# Adafruit_Cobbler_Plus.net
KiCad netlist of a schematic drawn in EAGLE
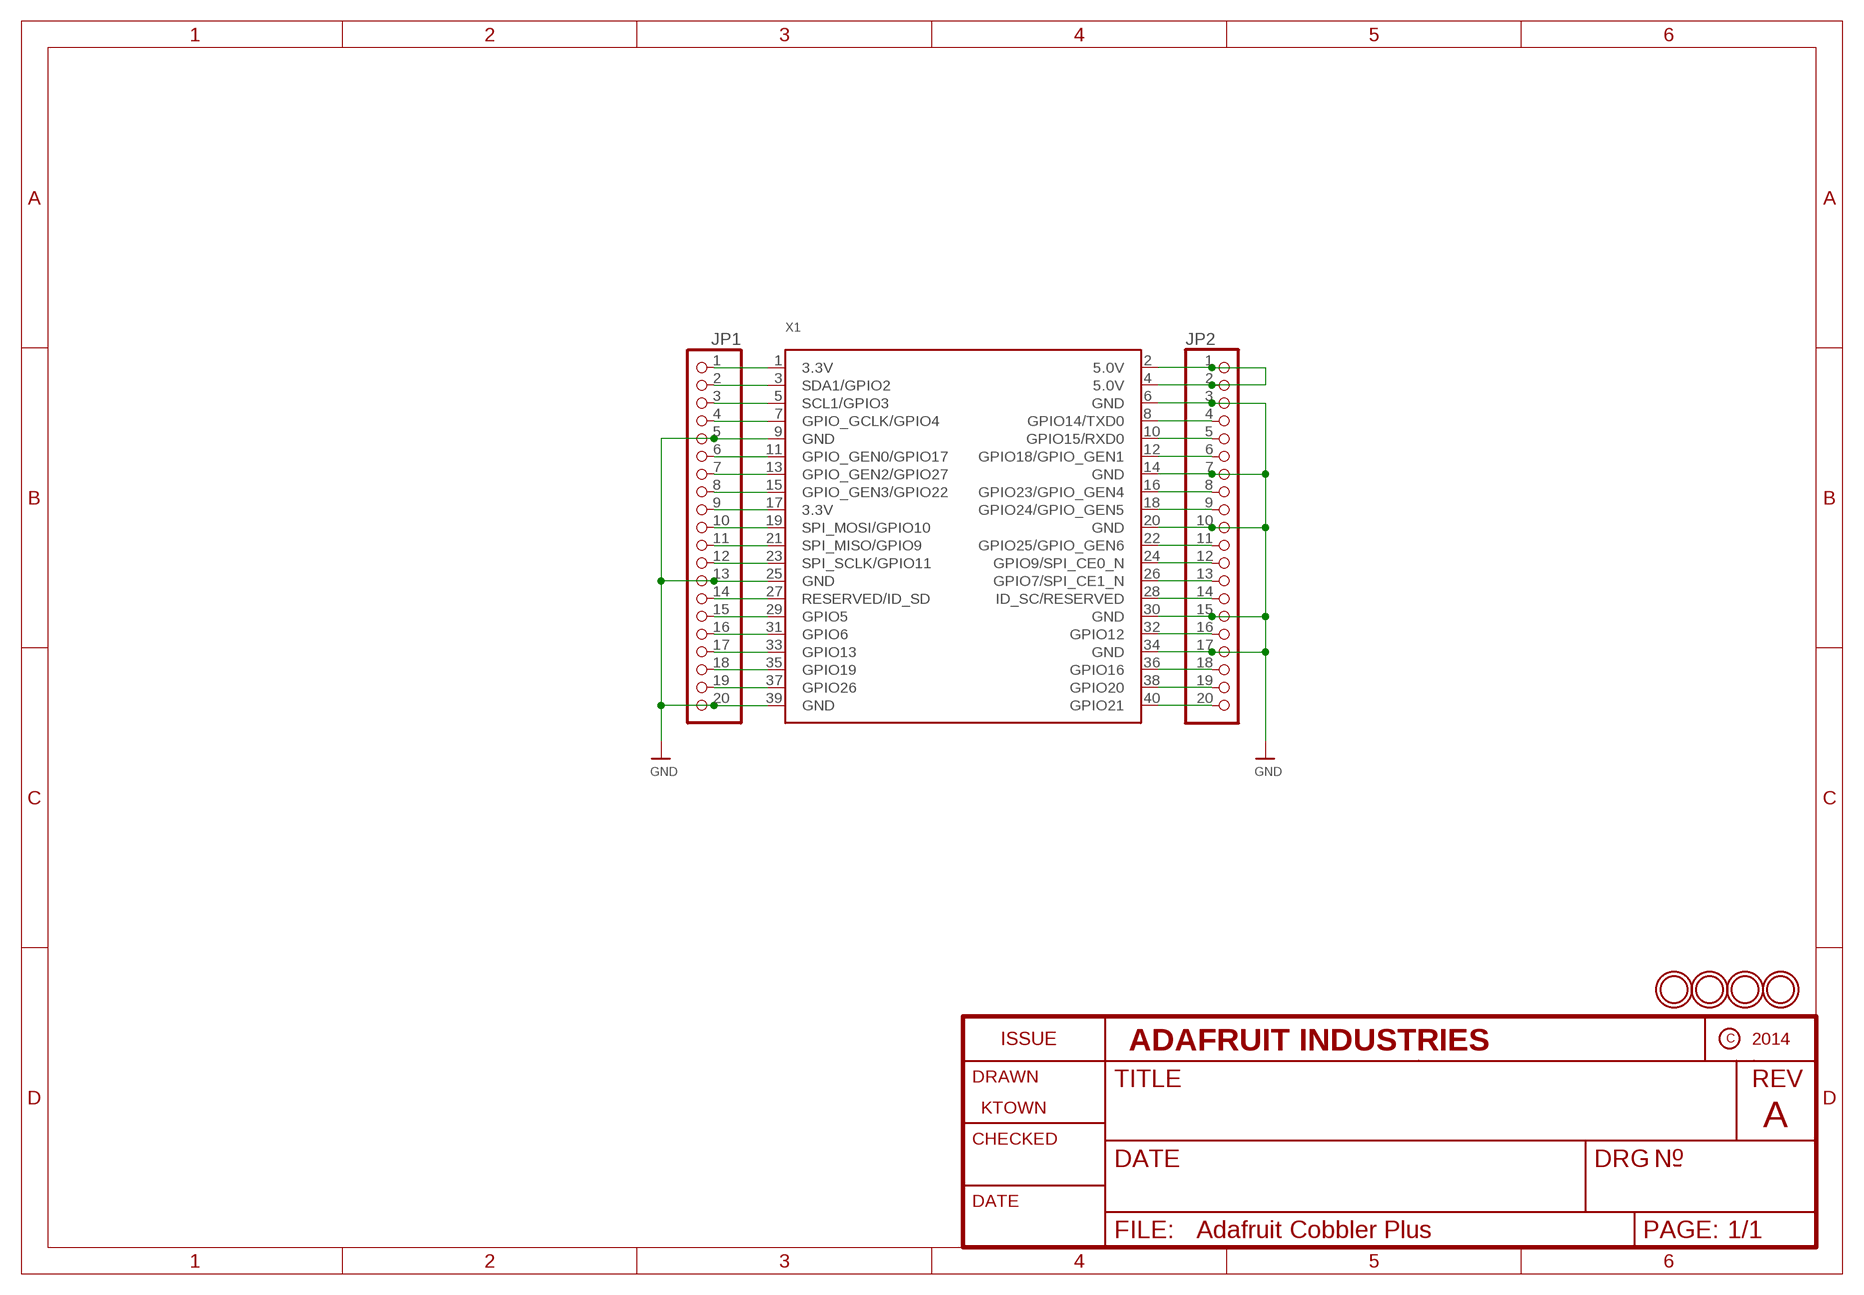
[diagram p0: schematic, sheet 1]

(export (version "E")
  (design (tool "Eeschema 10.0.6"))
  (components
    (comp (ref "JP1")
      (value "HEADER-1X20ROUND")
      (footprint "eagle-import:1X20_ROUND")
      (libsource (lib "eagle-import") (part "HEADER-1X20ROUND"))
    )
    (comp (ref "JP2")
      (value "HEADER-1X20ROUND")
      (footprint "eagle-import:1X20_ROUND")
      (libsource (lib "eagle-import") (part "HEADER-1X20ROUND"))
    )
    (comp (ref "U$1")
      (value "MOUNTINGHOLE2.5_THICK")
      (footprint "eagle-import:MOUNTINGHOLE_2.5_PLATED_THICK")
      (libsource (lib "eagle-import") (part "MOUNTINGHOLE2.5_THICK"))
    )
    (comp (ref "U$2")
      (value "MOUNTINGHOLE2.5_THICK")
      (footprint "eagle-import:MOUNTINGHOLE_2.5_PLATED_THICK")
      (libsource (lib "eagle-import") (part "MOUNTINGHOLE2.5_THICK"))
    )
    (comp (ref "U$3")
      (value "MOUNTINGHOLE2.5_THICK")
      (footprint "eagle-import:MOUNTINGHOLE_2.5_PLATED_THICK")
      (libsource (lib "eagle-import") (part "MOUNTINGHOLE2.5_THICK"))
    )
    (comp (ref "U$4")
      (value "MOUNTINGHOLE2.5_THICK")
      (footprint "eagle-import:MOUNTINGHOLE_2.5_PLATED_THICK")
      (libsource (lib "eagle-import") (part "MOUNTINGHOLE2.5_THICK"))
    )
    (comp (ref "X1")
      (value "RASPBERRYPI_B+_IDC")
      (footprint "eagle-import:RASPBERRYPI_B+_IDC")
      (libsource (lib "eagle-import") (part "RASPBERRYPI_B+_IDC"))
    )
  )
  (nets
    (net (code "1") (name "GND") (class "Default")
      (node (ref "JP1") (pin "13") (pinfunction "13_13") (pintype "passive"))
      (node (ref "JP1") (pin "20") (pinfunction "20_20") (pintype "passive"))
      (node (ref "JP1") (pin "5") (pinfunction "5_5") (pintype "passive"))
      (node (ref "JP2") (pin "10") (pinfunction "10_10") (pintype "passive"))
      (node (ref "JP2") (pin "15") (pinfunction "15_15") (pintype "passive"))
      (node (ref "JP2") (pin "17") (pinfunction "17_17") (pintype "passive"))
      (node (ref "JP2") (pin "3") (pinfunction "3_3") (pintype "passive"))
      (node (ref "JP2") (pin "7") (pinfunction "7_7") (pintype "passive"))
      (node (ref "X1") (pin "14") (pinfunction "GND_14") (pintype "power_in"))
      (node (ref "X1") (pin "20") (pinfunction "GND_20") (pintype "power_in"))
      (node (ref "X1") (pin "25") (pinfunction "GND_25") (pintype "power_in"))
      (node (ref "X1") (pin "30") (pinfunction "GND_30") (pintype "power_in"))
      (node (ref "X1") (pin "34") (pinfunction "GND_34") (pintype "power_in"))
      (node (ref "X1") (pin "39") (pinfunction "GND_39") (pintype "power_in"))
      (node (ref "X1") (pin "6") (pinfunction "GND_6") (pintype "power_in"))
      (node (ref "X1") (pin "9") (pinfunction "GND_9") (pintype "power_in"))
    )
    (net (code "2") (name "Net-(JP1-Pad1)") (class "Default")
      (node (ref "JP1") (pin "1") (pinfunction "1_1") (pintype "passive"))
      (node (ref "X1") (pin "1") (pinfunction "3.3V_1") (pintype "power_in"))
    )
    (net (code "3") (name "Net-(JP1-Pad9)") (class "Default")
      (node (ref "JP1") (pin "9") (pinfunction "9_9") (pintype "passive"))
      (node (ref "X1") (pin "17") (pinfunction "3.3V_17") (pintype "power_in"))
    )
    (net (code "4") (name "Net-(JP2-Pad1)") (class "Default")
      (node (ref "JP2") (pin "1") (pinfunction "1_1") (pintype "passive"))
      (node (ref "JP2") (pin "2") (pinfunction "2_2") (pintype "passive"))
      (node (ref "X1") (pin "2") (pinfunction "5.0V_2") (pintype "power_in"))
      (node (ref "X1") (pin "4") (pinfunction "5.0V_4") (pintype "power_in"))
    )
    (net (code "5") (name "Net-(X1-GPIO5)") (class "Default")
      (node (ref "JP1") (pin "15") (pinfunction "15_15") (pintype "passive"))
      (node (ref "X1") (pin "29") (pinfunction "GPIO5_29") (pintype "bidirectional"))
    )
    (net (code "6") (name "Net-(X1-GPIO6)") (class "Default")
      (node (ref "JP1") (pin "16") (pinfunction "16_16") (pintype "passive"))
      (node (ref "X1") (pin "31") (pinfunction "GPIO6_31") (pintype "bidirectional"))
    )
    (net (code "7") (name "Net-(X1-GPIO7{slash}SPI_CE1_N)") (class "Default")
      (node (ref "JP2") (pin "13") (pinfunction "13_13") (pintype "passive"))
      (node (ref "X1") (pin "26") (pinfunction "GPIO7/SPI_CE1_N_26") (pintype "bidirectional"))
    )
    (net (code "8") (name "Net-(X1-GPIO9{slash}SPI_CE0_N)") (class "Default")
      (node (ref "JP2") (pin "12") (pinfunction "12_12") (pintype "passive"))
      (node (ref "X1") (pin "24") (pinfunction "GPIO9/SPI_CE0_N_24") (pintype "bidirectional"))
    )
    (net (code "9") (name "Net-(X1-GPIO12)") (class "Default")
      (node (ref "JP2") (pin "16") (pinfunction "16_16") (pintype "passive"))
      (node (ref "X1") (pin "32") (pinfunction "GPIO12_32") (pintype "bidirectional"))
    )
    (net (code "10") (name "Net-(X1-GPIO13)") (class "Default")
      (node (ref "JP1") (pin "17") (pinfunction "17_17") (pintype "passive"))
      (node (ref "X1") (pin "33") (pinfunction "GPIO13_33") (pintype "bidirectional"))
    )
    (net (code "11") (name "Net-(X1-GPIO14{slash}TXD0)") (class "Default")
      (node (ref "JP2") (pin "4") (pinfunction "4_4") (pintype "passive"))
      (node (ref "X1") (pin "8") (pinfunction "GPIO14/TXD0_8") (pintype "bidirectional"))
    )
    (net (code "12") (name "Net-(X1-GPIO15{slash}RXD0)") (class "Default")
      (node (ref "JP2") (pin "5") (pinfunction "5_5") (pintype "passive"))
      (node (ref "X1") (pin "10") (pinfunction "GPIO15/RXD0_10") (pintype "bidirectional"))
    )
    (net (code "13") (name "Net-(X1-GPIO16)") (class "Default")
      (node (ref "JP2") (pin "18") (pinfunction "18_18") (pintype "passive"))
      (node (ref "X1") (pin "36") (pinfunction "GPIO16_36") (pintype "bidirectional"))
    )
    (net (code "14") (name "Net-(X1-GPIO18{slash}GPIO_GEN1)") (class "Default")
      (node (ref "JP2") (pin "6") (pinfunction "6_6") (pintype "passive"))
      (node (ref "X1") (pin "12") (pinfunction "GPIO18/GPIO_GEN1_12") (pintype "bidirectional"))
    )
    (net (code "15") (name "Net-(X1-GPIO19)") (class "Default")
      (node (ref "JP1") (pin "18") (pinfunction "18_18") (pintype "passive"))
      (node (ref "X1") (pin "35") (pinfunction "GPIO19_35") (pintype "bidirectional"))
    )
    (net (code "16") (name "Net-(X1-GPIO20)") (class "Default")
      (node (ref "JP2") (pin "19") (pinfunction "19_19") (pintype "passive"))
      (node (ref "X1") (pin "38") (pinfunction "GPIO20_38") (pintype "bidirectional"))
    )
    (net (code "17") (name "Net-(X1-GPIO21)") (class "Default")
      (node (ref "JP2") (pin "20") (pinfunction "20_20") (pintype "passive"))
      (node (ref "X1") (pin "40") (pinfunction "GPIO21_40") (pintype "bidirectional"))
    )
    (net (code "18") (name "Net-(X1-GPIO23{slash}GPIO_GEN4)") (class "Default")
      (node (ref "JP2") (pin "8") (pinfunction "8_8") (pintype "passive"))
      (node (ref "X1") (pin "16") (pinfunction "GPIO23/GPIO_GEN4_16") (pintype "bidirectional"))
    )
    (net (code "19") (name "Net-(X1-GPIO24{slash}GPIO_GEN5)") (class "Default")
      (node (ref "JP2") (pin "9") (pinfunction "9_9") (pintype "passive"))
      (node (ref "X1") (pin "18") (pinfunction "GPIO24/GPIO_GEN5_18") (pintype "bidirectional"))
    )
    (net (code "20") (name "Net-(X1-GPIO25{slash}GPIO_GEN6)") (class "Default")
      (node (ref "JP2") (pin "11") (pinfunction "11_11") (pintype "passive"))
      (node (ref "X1") (pin "22") (pinfunction "GPIO25/GPIO_GEN6_22") (pintype "bidirectional"))
    )
    (net (code "21") (name "Net-(X1-GPIO26)") (class "Default")
      (node (ref "JP1") (pin "19") (pinfunction "19_19") (pintype "passive"))
      (node (ref "X1") (pin "37") (pinfunction "GPIO26_37") (pintype "bidirectional"))
    )
    (net (code "22") (name "Net-(X1-GPIO_GCLK{slash}GPIO4)") (class "Default")
      (node (ref "JP1") (pin "4") (pinfunction "4_4") (pintype "passive"))
      (node (ref "X1") (pin "7") (pinfunction "GPIO_GCLK/GPIO4_7") (pintype "bidirectional"))
    )
    (net (code "23") (name "Net-(X1-GPIO_GEN0{slash}GPIO17)") (class "Default")
      (node (ref "JP1") (pin "6") (pinfunction "6_6") (pintype "passive"))
      (node (ref "X1") (pin "11") (pinfunction "GPIO_GEN0/GPIO17_11") (pintype "bidirectional"))
    )
    (net (code "24") (name "Net-(X1-GPIO_GEN2{slash}GPIO27)") (class "Default")
      (node (ref "JP1") (pin "7") (pinfunction "7_7") (pintype "passive"))
      (node (ref "X1") (pin "13") (pinfunction "GPIO_GEN2/GPIO27_13") (pintype "bidirectional"))
    )
    (net (code "25") (name "Net-(X1-GPIO_GEN3{slash}GPIO22)") (class "Default")
      (node (ref "JP1") (pin "8") (pinfunction "8_8") (pintype "passive"))
      (node (ref "X1") (pin "15") (pinfunction "GPIO_GEN3/GPIO22_15") (pintype "bidirectional"))
    )
    (net (code "26") (name "Net-(X1-ID_SC{slash}RESERVED)") (class "Default")
      (node (ref "JP2") (pin "14") (pinfunction "14_14") (pintype "passive"))
      (node (ref "X1") (pin "28") (pinfunction "ID_SC/RESERVED_28") (pintype "bidirectional"))
    )
    (net (code "27") (name "Net-(X1-RESERVED{slash}ID_SD)") (class "Default")
      (node (ref "JP1") (pin "14") (pinfunction "14_14") (pintype "passive"))
      (node (ref "X1") (pin "27") (pinfunction "RESERVED/ID_SD_27") (pintype "bidirectional"))
    )
    (net (code "28") (name "Net-(X1-SCL1{slash}GPIO3)") (class "Default")
      (node (ref "JP1") (pin "3") (pinfunction "3_3") (pintype "passive"))
      (node (ref "X1") (pin "5") (pinfunction "SCL1/GPIO3_5") (pintype "bidirectional"))
    )
    (net (code "29") (name "Net-(X1-SDA1{slash}GPIO2)") (class "Default")
      (node (ref "JP1") (pin "2") (pinfunction "2_2") (pintype "passive"))
      (node (ref "X1") (pin "3") (pinfunction "SDA1/GPIO2_3") (pintype "bidirectional"))
    )
    (net (code "30") (name "Net-(X1-SPI_MISO{slash}GPIO9)") (class "Default")
      (node (ref "JP1") (pin "11") (pinfunction "11_11") (pintype "passive"))
      (node (ref "X1") (pin "21") (pinfunction "SPI_MISO/GPIO9_21") (pintype "input"))
    )
    (net (code "31") (name "Net-(X1-SPI_MOSI{slash}GPIO10)") (class "Default")
      (node (ref "JP1") (pin "10") (pinfunction "10_10") (pintype "passive"))
      (node (ref "X1") (pin "19") (pinfunction "SPI_MOSI/GPIO10_19") (pintype "bidirectional"))
    )
    (net (code "32") (name "Net-(X1-SPI_SCLK{slash}GPIO11)") (class "Default")
      (node (ref "JP1") (pin "12") (pinfunction "12_12") (pintype "passive"))
      (node (ref "X1") (pin "23") (pinfunction "SPI_SCLK/GPIO11_23") (pintype "bidirectional"))
    )
  )
)
